# smoothie_ramps.net
KiCad netlist of a schematic drawn in EAGLE
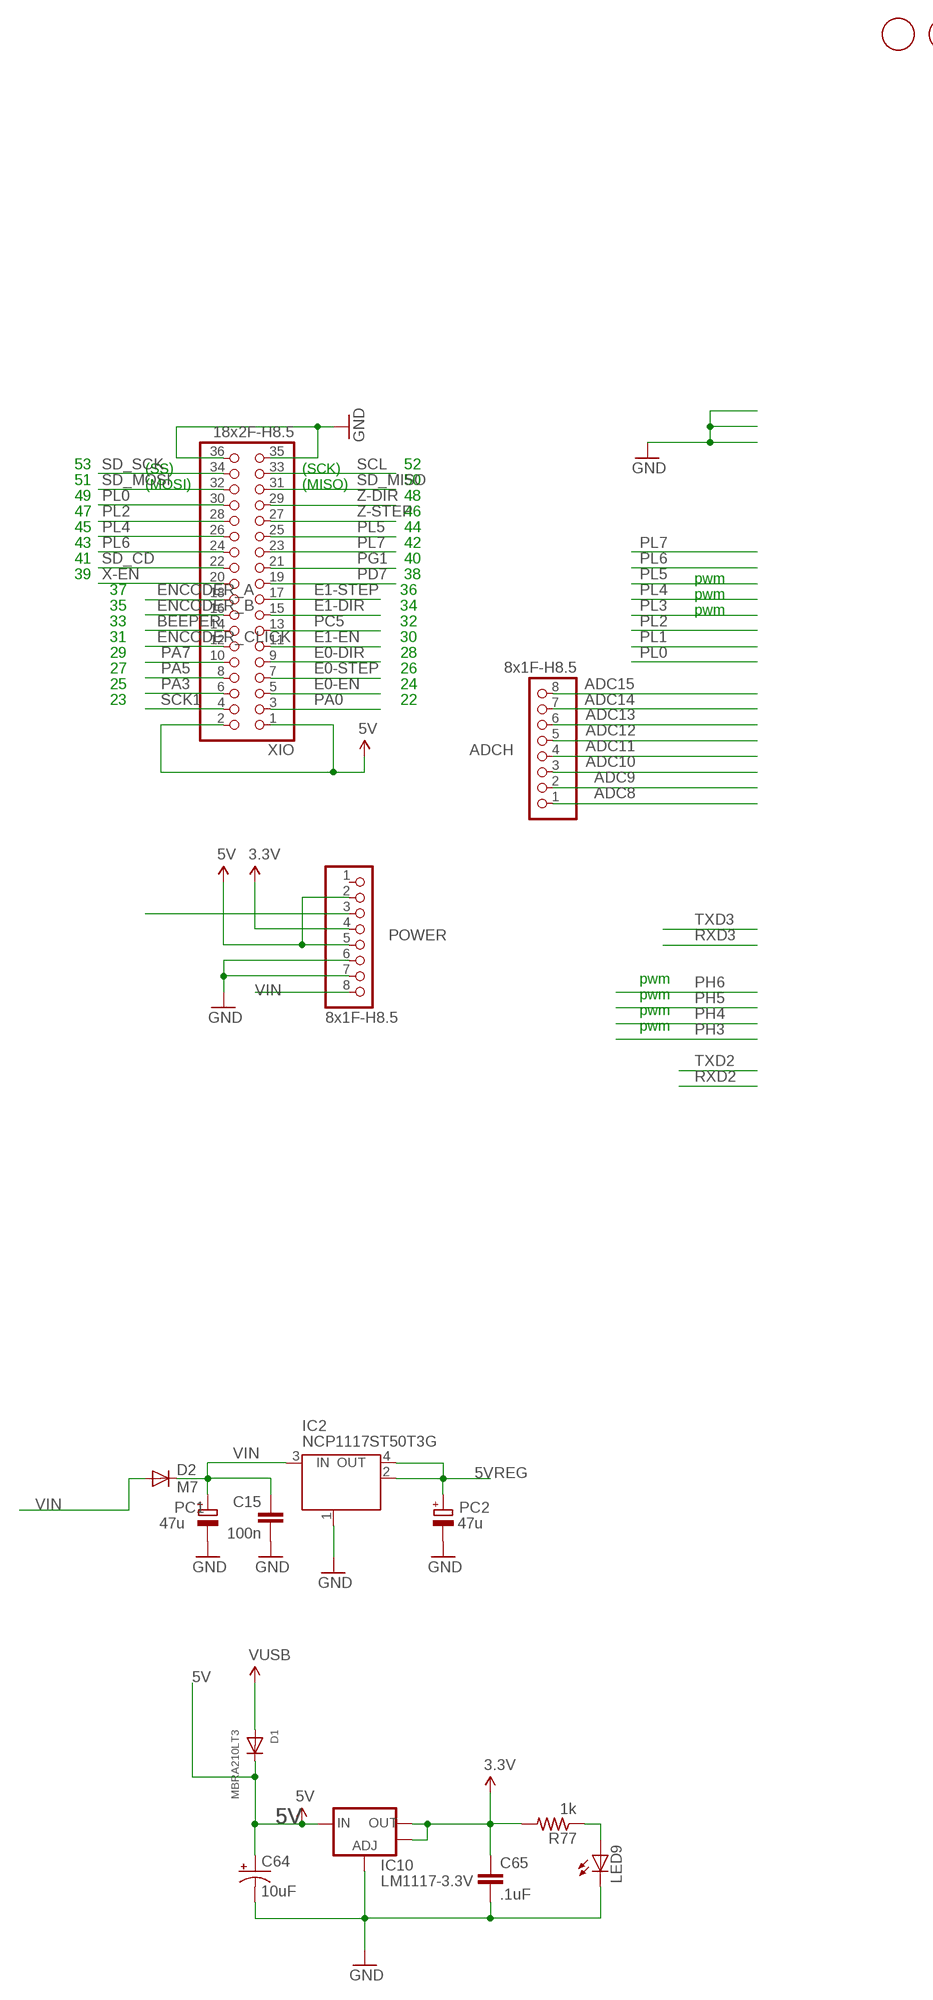
[diagram p0: schematic, sheet 1, part 1 of 2]
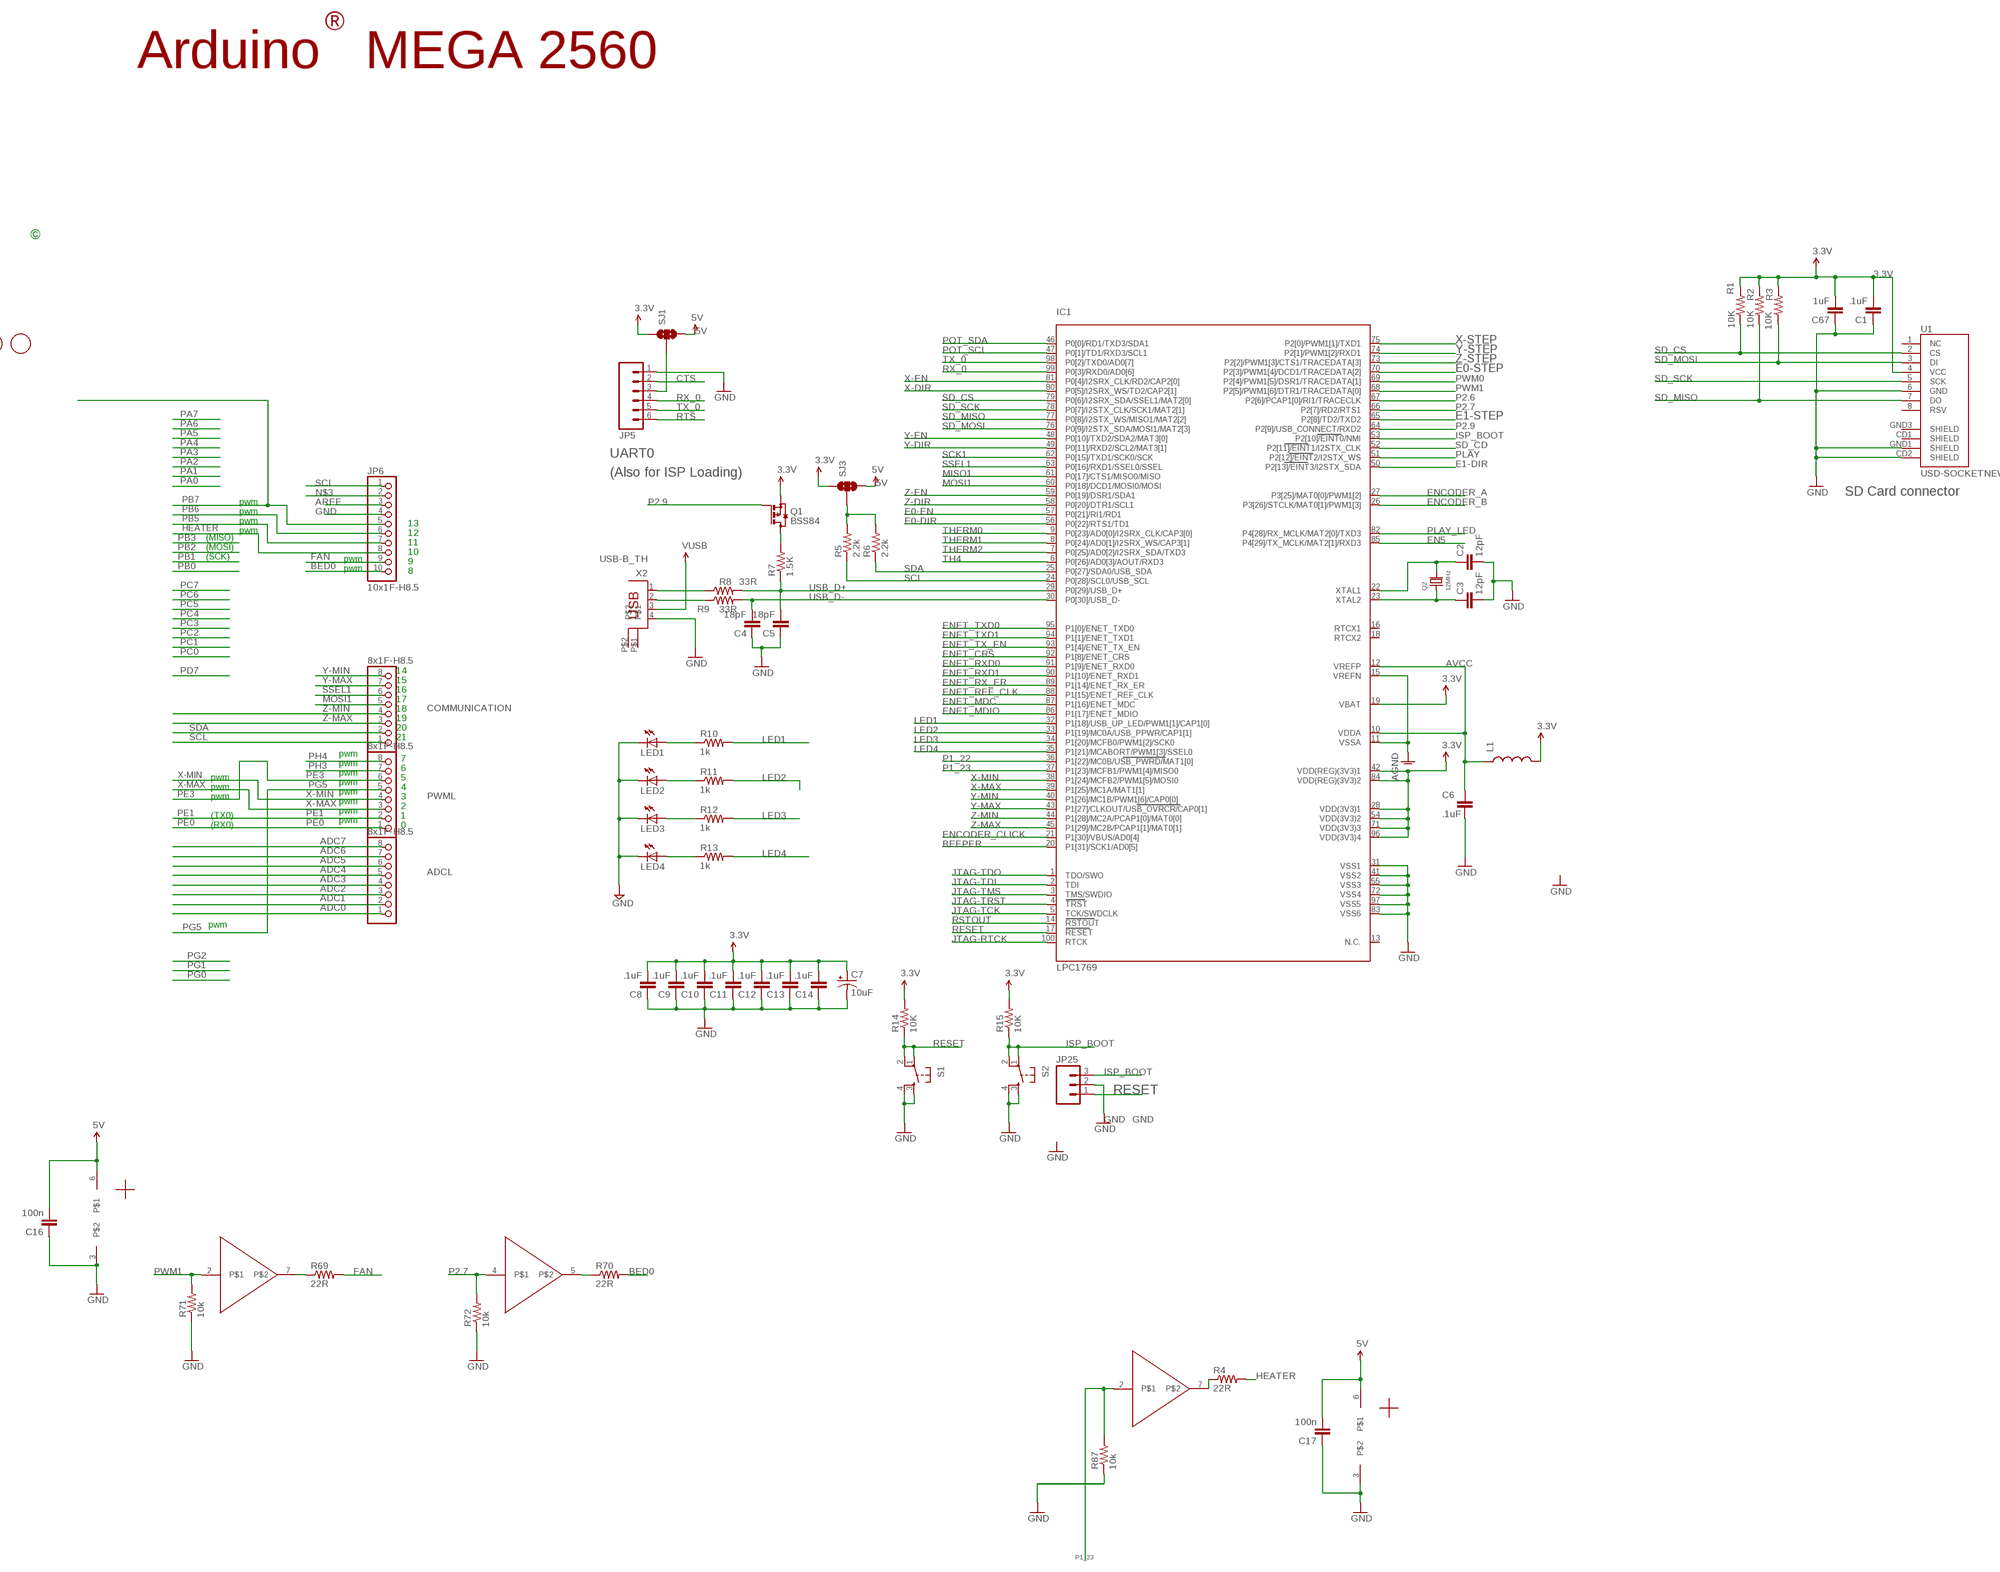
[diagram p1: schematic, sheet 1, part 2 of 2]

(export (version "E")
  (design (tool "Eeschema 10.0.6"))
  (components
    (comp (ref "ADCH")
      (value "8x1F-H8.5")
      (footprint "eagle-import:1X08")
      (libsource (lib "eagle-import") (part "PINHD-1X8"))
    )
    (comp (ref "ADCL")
      (value "8x1F-H8.5")
      (footprint "eagle-import:1X08")
      (libsource (lib "eagle-import") (part "PINHD-1X8"))
    )
    (comp (ref "C1")
      (value ".1uF")
      (footprint "eagle-import:C0603")
      (libsource (lib "eagle-import") (part "resistor_C-EUC0603"))
    )
    (comp (ref "C2")
      (value "12pF")
      (footprint "eagle-import:C0603")
      (libsource (lib "eagle-import") (part "rcl_C-EUC0603"))
    )
    (comp (ref "C3")
      (value "12pF")
      (footprint "eagle-import:C0603")
      (libsource (lib "eagle-import") (part "rcl_C-EUC0603"))
    )
    (comp (ref "C4")
      (value "18pF")
      (footprint "eagle-import:C0603")
      (libsource (lib "eagle-import") (part "rcl_C-EUC0603"))
    )
    (comp (ref "C5")
      (value "18pF")
      (footprint "eagle-import:C0603")
      (libsource (lib "eagle-import") (part "rcl_C-EUC0603"))
    )
    (comp (ref "C6")
      (value ".1uF")
      (footprint "eagle-import:C0603")
      (libsource (lib "eagle-import") (part "rcl_C-EUC0603"))
    )
    (comp (ref "C7")
      (value "10uF")
      (footprint "eagle-import:EIA3216")
      (libsource (lib "eagle-import") (part "CAP_POL1206"))
    )
    (comp (ref "C8")
      (value ".1uF")
      (footprint "eagle-import:C0603")
      (libsource (lib "eagle-import") (part "rcl_C-EUC0603"))
    )
    (comp (ref "C9")
      (value ".1uF")
      (footprint "eagle-import:C0603")
      (libsource (lib "eagle-import") (part "rcl_C-EUC0603"))
    )
    (comp (ref "C10")
      (value ".1uF")
      (footprint "eagle-import:C0603")
      (libsource (lib "eagle-import") (part "rcl_C-EUC0603"))
    )
    (comp (ref "C11")
      (value ".1uF")
      (footprint "eagle-import:C0603")
      (libsource (lib "eagle-import") (part "rcl_C-EUC0603"))
    )
    (comp (ref "C12")
      (value ".1uF")
      (footprint "eagle-import:C0603")
      (libsource (lib "eagle-import") (part "rcl_C-EUC0603"))
    )
    (comp (ref "C13")
      (value ".1uF")
      (footprint "eagle-import:C0603")
      (libsource (lib "eagle-import") (part "rcl_C-EUC0603"))
    )
    (comp (ref "C14")
      (value ".1uF")
      (footprint "eagle-import:C0603")
      (libsource (lib "eagle-import") (part "rcl_C-EUC0603"))
    )
    (comp (ref "C15")
      (value "100n")
      (footprint "eagle-import:C0603-ROUND")
      (libsource (lib "eagle-import") (part "C-EU0603-RND"))
    )
    (comp (ref "C16")
      (value "100n")
      (footprint "eagle-import:C0603")
      (libsource (lib "eagle-import") (part "rcl_C-EUC0603"))
    )
    (comp (ref "C17")
      (value "100n")
      (footprint "eagle-import:C0603")
      (libsource (lib "eagle-import") (part "rcl_C-EUC0603"))
    )
    (comp (ref "C64")
      (value "10uF")
      (footprint "eagle-import:EIA3216")
      (libsource (lib "eagle-import") (part "CAP_POL1206"))
    )
    (comp (ref "C65")
      (value ".1uF")
      (footprint "eagle-import:C0603")
      (libsource (lib "eagle-import") (part "resistor_C-EUC0603"))
    )
    (comp (ref "C67")
      (value "1uF")
      (footprint "eagle-import:C0805")
      (libsource (lib "eagle-import") (part "resistor_C-EUC0805"))
    )
    (comp (ref "COMMUNICATION")
      (value "8x1F-H8.5")
      (footprint "eagle-import:1X08")
      (libsource (lib "eagle-import") (part "PINHD-1X8"))
    )
    (comp (ref "D1")
      (value "MBRA210LT3")
      (footprint "eagle-import:SMADIODE")
      (libsource (lib "eagle-import") (part "DIODESMA"))
    )
    (comp (ref "D2")
      (value "M7")
      (footprint "eagle-import:SMB")
      (libsource (lib "eagle-import") (part "DIODE-SMB"))
    )
    (comp (ref "FD2")
      (value "FIDUCIALMOUNT")
      (footprint "eagle-import:FIDUCIA-MOUNT")
      (libsource (lib "eagle-import") (part "FIDUCIALMOUNT"))
    )
    (comp (ref "FD3")
      (value "FIDUCIALMOUNT")
      (footprint "eagle-import:FIDUCIA-MOUNT")
      (libsource (lib "eagle-import") (part "FIDUCIALMOUNT"))
    )
    (comp (ref "IC1")
      (value "LPC1769")
      (footprint "eagle-import:LQFP100")
      (libsource (lib "eagle-import") (part "LPC1768"))
    )
    (comp (ref "IC2")
      (value "NCP1117ST50T3G")
      (footprint "eagle-import:SOT223")
      (libsource (lib "eagle-import") (part "MC33269ST-3.3T3"))
    )
    (comp (ref "IC10")
      (value "LM1117-3.3V")
      (footprint "eagle-import:SOT223")
      (libsource (lib "eagle-import") (part "V_REG_LM1117SOT223"))
    )
    (comp (ref "IC14")
      (value "TC4427")
      (footprint "eagle-import:SOIC8")
      (libsource (lib "eagle-import") (part "TC4427"))
    )
    (comp (ref "IC15")
      (value "TC4427")
      (footprint "eagle-import:SOIC8")
      (libsource (lib "eagle-import") (part "TC4427"))
    )
    (comp (ref "JP5")
      (value "M06POLAR")
      (footprint "eagle-import:MOLEX-1X6")
      (libsource (lib "eagle-import") (part "M06POLAR"))
    )
    (comp (ref "JP6")
      (value "10x1F-H8.5")
      (footprint "eagle-import:1X10")
      (libsource (lib "eagle-import") (part "PINHD-1X10_ARD"))
    )
    (comp (ref "JP25")
      (value "M03PTH")
      (footprint "eagle-import:1X03")
      (libsource (lib "eagle-import") (part "M03PTH"))
    )
    (comp (ref "L1")
      (value "INDUCTOR0603")
      (footprint "eagle-import:0603")
      (libsource (lib "eagle-import") (part "INDUCTOR0603"))
    )
    (comp (ref "LED1")
      (value "LEDCHIP-LED0805")
      (footprint "eagle-import:CHIP-LED0805")
      (libsource (lib "eagle-import") (part "LEDCHIP-LED0805"))
    )
    (comp (ref "LED2")
      (value "LEDCHIP-LED0805")
      (footprint "eagle-import:CHIP-LED0805")
      (libsource (lib "eagle-import") (part "LEDCHIP-LED0805"))
    )
    (comp (ref "LED3")
      (value "LEDCHIP-LED0805")
      (footprint "eagle-import:CHIP-LED0805")
      (libsource (lib "eagle-import") (part "LEDCHIP-LED0805"))
    )
    (comp (ref "LED4")
      (value "LEDCHIP-LED0805")
      (footprint "eagle-import:CHIP-LED0805")
      (libsource (lib "eagle-import") (part "LEDCHIP-LED0805"))
    )
    (comp (ref "LED9")
      (value "LEDCHIP-LED0805")
      (footprint "eagle-import:CHIP-LED0805")
      (libsource (lib "eagle-import") (part "LEDCHIP-LED0805"))
    )
    (comp (ref "PC1")
      (value "47u")
      (footprint "eagle-import:PANASONIC_D")
      (libsource (lib "eagle-import") (part "CPOL-EUD"))
    )
    (comp (ref "PC2")
      (value "47u")
      (footprint "eagle-import:PANASONIC_D")
      (libsource (lib "eagle-import") (part "CPOL-EUD"))
    )
    (comp (ref "POWER")
      (value "8x1F-H8.5")
      (footprint "eagle-import:1X08")
      (libsource (lib "eagle-import") (part "PINHD-1X8"))
    )
    (comp (ref "PWML")
      (value "8x1F-H8.5")
      (footprint "eagle-import:1X08")
      (libsource (lib "eagle-import") (part "PINHD-1X8"))
    )
    (comp (ref "Q1")
      (value "BSS84")
      (footprint "eagle-import:SOT23")
      (libsource (lib "eagle-import") (part "BSS84"))
    )
    (comp (ref "Q2")
      (value "12MHz")
      (footprint "eagle-import:CRYSTAL_3.2X2.5")
      (libsource (lib "eagle-import") (part "CRYSTALTHIN"))
    )
    (comp (ref "R1")
      (value "10K")
      (footprint "eagle-import:R0603")
      (libsource (lib "eagle-import") (part "R-US_R0603"))
    )
    (comp (ref "R2")
      (value "10K")
      (footprint "eagle-import:R0603")
      (libsource (lib "eagle-import") (part "R-US_R0603"))
    )
    (comp (ref "R3")
      (value "10K")
      (footprint "eagle-import:R0603")
      (libsource (lib "eagle-import") (part "R-US_R0603"))
    )
    (comp (ref "R4")
      (value "22R")
      (footprint "eagle-import:R0603")
      (libsource (lib "eagle-import") (part "R-US_R0603"))
    )
    (comp (ref "R5")
      (value "2.2k")
      (footprint "eagle-import:R0603")
      (libsource (lib "eagle-import") (part "R-US_R0603"))
    )
    (comp (ref "R6")
      (value "2.2k")
      (footprint "eagle-import:R0603")
      (libsource (lib "eagle-import") (part "R-US_R0603"))
    )
    (comp (ref "R7")
      (value "1.5K")
      (footprint "eagle-import:R0603")
      (libsource (lib "eagle-import") (part "R-US_R0603"))
    )
    (comp (ref "R8")
      (value "33R")
      (footprint "eagle-import:R0603")
      (libsource (lib "eagle-import") (part "R-US_R0603"))
    )
    (comp (ref "R9")
      (value "33R")
      (footprint "eagle-import:R0603")
      (libsource (lib "eagle-import") (part "R-US_R0603"))
    )
    (comp (ref "R10")
      (value "1k")
      (footprint "eagle-import:R0603")
      (libsource (lib "eagle-import") (part "R-US_R0603"))
    )
    (comp (ref "R11")
      (value "1k")
      (footprint "eagle-import:R0603")
      (libsource (lib "eagle-import") (part "R-US_R0603"))
    )
    (comp (ref "R12")
      (value "1k")
      (footprint "eagle-import:R0603")
      (libsource (lib "eagle-import") (part "R-US_R0603"))
    )
    (comp (ref "R13")
      (value "1k")
      (footprint "eagle-import:R0603")
      (libsource (lib "eagle-import") (part "R-US_R0603"))
    )
    (comp (ref "R14")
      (value "10K")
      (footprint "eagle-import:R0603")
      (libsource (lib "eagle-import") (part "R-US_R0603"))
    )
    (comp (ref "R15")
      (value "10K")
      (footprint "eagle-import:R0603")
      (libsource (lib "eagle-import") (part "R-US_R0603"))
    )
    (comp (ref "R69")
      (value "22R")
      (footprint "eagle-import:R0603")
      (libsource (lib "eagle-import") (part "R-US_R0603"))
    )
    (comp (ref "R70")
      (value "22R")
      (footprint "eagle-import:R0603")
      (libsource (lib "eagle-import") (part "R-US_R0603"))
    )
    (comp (ref "R71")
      (value "10k")
      (footprint "eagle-import:R0603")
      (libsource (lib "eagle-import") (part "R-US_R0603"))
    )
    (comp (ref "R72")
      (value "10k")
      (footprint "eagle-import:R0603")
      (libsource (lib "eagle-import") (part "R-US_R0603"))
    )
    (comp (ref "R77")
      (value "1k")
      (footprint "eagle-import:R0603")
      (libsource (lib "eagle-import") (part "R-US_R0603"))
    )
    (comp (ref "R87")
      (value "10k")
      (footprint "eagle-import:R0603")
      (libsource (lib "eagle-import") (part "R-US_R0603"))
    )
    (comp (ref "S1")
      (value "TAC_SWITCHSMD")
      (footprint "eagle-import:TACTILE_SWITCH_SMD")
      (libsource (lib "eagle-import") (part "TAC_SWITCHSMD"))
    )
    (comp (ref "S2")
      (value "TAC_SWITCHSMD")
      (footprint "eagle-import:TACTILE_SWITCH_SMD")
      (libsource (lib "eagle-import") (part "TAC_SWITCHSMD"))
    )
    (comp (ref "SJ1")
      (value "SOLDERJUMPER_2WAYS")
      (footprint "eagle-import:SJ_3")
      (libsource (lib "eagle-import") (part "SOLDERJUMPER_2WAYS"))
    )
    (comp (ref "SJ3")
      (value "SOLDERJUMPER_2WAYS")
      (footprint "eagle-import:SJ_3")
      (libsource (lib "eagle-import") (part "SOLDERJUMPER_2WAYS"))
    )
    (comp (ref "U1")
      (value "USD-SOCKETNEW")
      (footprint "eagle-import:MICRO-SD-SOCKET-PP")
      (libsource (lib "eagle-import") (part "USD-SOCKETNEW"))
    )
    (comp (ref "X2")
      (value "USB-B_TH")
      (footprint "eagle-import:PN61729")
      (libsource (lib "eagle-import") (part "PN61729"))
    )
    (comp (ref "XIO")
      (value "18x2F-H8.5")
      (footprint "eagle-import:2X18")
      (libsource (lib "eagle-import") (part "PINHD-2X18"))
    )
  )
  (nets
    (net (code "1") (name "/5VREG") (class "Default")
      (node (ref "IC2") (pin "2") (pinfunction "OUT_2") (pintype "passive"))
      (node (ref "IC2") (pin "4") (pinfunction "OUT_4") (pintype "passive"))
      (node (ref "PC2") (pin "+") (pinfunction "+_+") (pintype "passive"))
    )
    (net (code "2") (name "/ADC0") (class "Default")
      (node (ref "ADCL") (pin "1") (pinfunction "1_1") (pintype "passive"))
    )
    (net (code "3") (name "/ADC1") (class "Default")
      (node (ref "ADCL") (pin "2") (pinfunction "2_2") (pintype "passive"))
    )
    (net (code "4") (name "/ADC2") (class "Default")
      (node (ref "ADCL") (pin "3") (pinfunction "3_3") (pintype "passive"))
    )
    (net (code "5") (name "/ADC3") (class "Default")
      (node (ref "ADCL") (pin "4") (pinfunction "4_4") (pintype "passive"))
    )
    (net (code "6") (name "/ADC4") (class "Default")
      (node (ref "ADCL") (pin "5") (pinfunction "5_5") (pintype "passive"))
    )
    (net (code "7") (name "/ADC5") (class "Default")
      (node (ref "ADCL") (pin "6") (pinfunction "6_6") (pintype "passive"))
    )
    (net (code "8") (name "/ADC6") (class "Default")
      (node (ref "ADCL") (pin "7") (pinfunction "7_7") (pintype "passive"))
    )
    (net (code "9") (name "/ADC7") (class "Default")
      (node (ref "ADCL") (pin "8") (pinfunction "8_8") (pintype "passive"))
    )
    (net (code "10") (name "/ADC8") (class "Default")
      (node (ref "ADCH") (pin "1") (pinfunction "1_1") (pintype "passive"))
    )
    (net (code "11") (name "/ADC9") (class "Default")
      (node (ref "ADCH") (pin "2") (pinfunction "2_2") (pintype "passive"))
    )
    (net (code "12") (name "/ADC10") (class "Default")
      (node (ref "ADCH") (pin "3") (pinfunction "3_3") (pintype "passive"))
    )
    (net (code "13") (name "/ADC11") (class "Default")
      (node (ref "ADCH") (pin "4") (pinfunction "4_4") (pintype "passive"))
    )
    (net (code "14") (name "/ADC12") (class "Default")
      (node (ref "ADCH") (pin "5") (pinfunction "5_5") (pintype "passive"))
    )
    (net (code "15") (name "/ADC13") (class "Default")
      (node (ref "ADCH") (pin "6") (pinfunction "6_6") (pintype "passive"))
    )
    (net (code "16") (name "/ADC14") (class "Default")
      (node (ref "ADCH") (pin "7") (pinfunction "7_7") (pintype "passive"))
    )
    (net (code "17") (name "/ADC15") (class "Default")
      (node (ref "ADCH") (pin "8") (pinfunction "8_8") (pintype "passive"))
    )
    (net (code "18") (name "/AREF") (class "Default")
      (node (ref "JP6") (pin "3") (pinfunction "3_3") (pintype "passive"))
    )
    (net (code "19") (name "/AVCC") (class "Default")
      (node (ref "C6") (pin "1") (pinfunction "1_1") (pintype "passive"))
      (node (ref "IC1") (pin "10") (pinfunction "VDDA_10") (pintype "bidirectional"))
      (node (ref "IC1") (pin "12") (pinfunction "VREFP_12") (pintype "bidirectional"))
      (node (ref "L1") (pin "1") (pinfunction "1_1") (pintype "passive"))
    )
    (net (code "20") (name "/BED0") (class "Default")
      (node (ref "JP6") (pin "10") (pinfunction "10_10") (pintype "passive"))
      (node (ref "R70") (pin "2") (pinfunction "2_2") (pintype "passive"))
    )
    (net (code "21") (name "/BEEPER") (class "Default")
      (node (ref "IC1") (pin "20") (pinfunction "P1[31]/SCK1/AD0[5]_20") (pintype "bidirectional"))
      (node (ref "XIO") (pin "14") (pinfunction "14_14") (pintype "passive"))
    )
    (net (code "22") (name "/CTS") (class "Default")
      (node (ref "JP5") (pin "2") (pinfunction "2_2") (pintype "passive"))
    )
    (net (code "23") (name "/E0-DIR") (class "Default")
      (node (ref "IC1") (pin "56") (pinfunction "P0[22]/RTS1/TD1_56") (pintype "bidirectional"))
      (node (ref "XIO") (pin "9") (pinfunction "9_9") (pintype "passive"))
    )
    (net (code "24") (name "/E0-EN") (class "Default")
      (node (ref "IC1") (pin "57") (pinfunction "P0[21]/RI1/RD1_57") (pintype "bidirectional"))
      (node (ref "XIO") (pin "5") (pinfunction "5_5") (pintype "passive"))
    )
    (net (code "25") (name "/E0-STEP") (class "Default")
      (node (ref "IC1") (pin "70") (pinfunction "P2[3]/PWM1[4]/DCD1/TRACEDATA[2]_70") (pintype "bidirectional"))
      (node (ref "XIO") (pin "7") (pinfunction "7_7") (pintype "passive"))
    )
    (net (code "26") (name "/E1-DIR") (class "Default")
      (node (ref "IC1") (pin "50") (pinfunction "P2[13]/EINT3/I2STX_SDA_50") (pintype "bidirectional"))
      (node (ref "XIO") (pin "15") (pinfunction "15_15") (pintype "passive"))
    )
    (net (code "27") (name "/E1-EN") (class "Default")
      (node (ref "XIO") (pin "11") (pinfunction "11_11") (pintype "passive"))
    )
    (net (code "28") (name "/E1-STEP") (class "Default")
      (node (ref "IC1") (pin "65") (pinfunction "P2[8]/TD2/TXD2_65") (pintype "bidirectional"))
      (node (ref "XIO") (pin "17") (pinfunction "17_17") (pintype "passive"))
    )
    (net (code "29") (name "/EN5") (class "Default")
      (node (ref "IC1") (pin "85") (pinfunction "P4[29]/TX_MCLK/MAT2[1]/RXD3_85") (pintype "bidirectional"))
    )
    (net (code "30") (name "/ENCODER_A") (class "Default")
      (node (ref "IC1") (pin "27") (pinfunction "P3[25]/MAT0[0]/PWM1[2]_27") (pintype "bidirectional"))
      (node (ref "XIO") (pin "18") (pinfunction "18_18") (pintype "passive"))
    )
    (net (code "31") (name "/ENCODER_B") (class "Default")
      (node (ref "IC1") (pin "26") (pinfunction "P3[26]/STCLK/MAT0[1]/PWM1[3]_26") (pintype "bidirectional"))
      (node (ref "XIO") (pin "16") (pinfunction "16_16") (pintype "passive"))
    )
    (net (code "32") (name "/ENCODER_CLICK") (class "Default")
      (node (ref "IC1") (pin "21") (pinfunction "P1[30]/VBUS/AD0[4]_21") (pintype "bidirectional"))
      (node (ref "XIO") (pin "12") (pinfunction "12_12") (pintype "passive"))
    )
    (net (code "33") (name "/ENET_CRS") (class "Default")
      (node (ref "IC1") (pin "92") (pinfunction "P1[8]/ENET_CRS_92") (pintype "bidirectional"))
    )
    (net (code "34") (name "/ENET_MDC") (class "Default")
      (node (ref "IC1") (pin "87") (pinfunction "P1[16]/ENET_MDC_87") (pintype "bidirectional"))
    )
    (net (code "35") (name "/ENET_MDIO") (class "Default")
      (node (ref "IC1") (pin "86") (pinfunction "P1[17]/ENET_MDIO_86") (pintype "bidirectional"))
    )
    (net (code "36") (name "/ENET_REF_CLK") (class "Default")
      (node (ref "IC1") (pin "88") (pinfunction "P1[15]/ENET_REF_CLK_88") (pintype "bidirectional"))
    )
    (net (code "37") (name "/ENET_RXD0") (class "Default")
      (node (ref "IC1") (pin "91") (pinfunction "P1[9]/ENET_RXD0_91") (pintype "bidirectional"))
    )
    (net (code "38") (name "/ENET_RXD1") (class "Default")
      (node (ref "IC1") (pin "90") (pinfunction "P1[10]/ENET_RXD1_90") (pintype "bidirectional"))
    )
    (net (code "39") (name "/ENET_RX_ER") (class "Default")
      (node (ref "IC1") (pin "89") (pinfunction "P1[14]/ENET_RX_ER_89") (pintype "bidirectional"))
    )
    (net (code "40") (name "/ENET_TXD0") (class "Default")
      (node (ref "IC1") (pin "95") (pinfunction "P1[0]/ENET_TXD0_95") (pintype "bidirectional"))
    )
    (net (code "41") (name "/ENET_TXD1") (class "Default")
      (node (ref "IC1") (pin "94") (pinfunction "P1[1]/ENET_TXD1_94") (pintype "bidirectional"))
    )
    (net (code "42") (name "/ENET_TX_EN") (class "Default")
      (node (ref "IC1") (pin "93") (pinfunction "P1[4]/ENET_TX_EN_93") (pintype "bidirectional"))
    )
    (net (code "43") (name "/FAN") (class "Default")
      (node (ref "JP6") (pin "9") (pinfunction "9_9") (pintype "passive"))
      (node (ref "R69") (pin "2") (pinfunction "2_2") (pintype "passive"))
    )
    (net (code "44") (name "/HEATER") (class "Default")
      (node (ref "JP6") (pin "8") (pinfunction "8_8") (pintype "passive"))
      (node (ref "R4") (pin "2") (pinfunction "2_2") (pintype "passive"))
    )
    (net (code "45") (name "/ISP_BOOT") (class "Default")
      (node (ref "IC1") (pin "53") (pinfunction "P2[10]/EINT0/NMI_53") (pintype "bidirectional"))
      (node (ref "JP25") (pin "3") (pinfunction "3_3") (pintype "passive"))
      (node (ref "R15") (pin "1") (pinfunction "1_1") (pintype "passive"))
      (node (ref "S2") (pin "1") (pinfunction "1_1") (pintype "passive"))
      (node (ref "S2") (pin "2") (pinfunction "2_2") (pintype "passive"))
    )
    (net (code "46") (name "/JTAG-RTCK") (class "Default")
      (node (ref "IC1") (pin "100") (pinfunction "RTCK_100") (pintype "bidirectional"))
    )
    (net (code "47") (name "/JTAG-TCK") (class "Default")
      (node (ref "IC1") (pin "5") (pinfunction "TCK/SWDCLK_5") (pintype "bidirectional"))
    )
    (net (code "48") (name "/JTAG-TDI") (class "Default")
      (node (ref "IC1") (pin "2") (pinfunction "TDI_2") (pintype "bidirectional"))
    )
    (net (code "49") (name "/JTAG-TDO") (class "Default")
      (node (ref "IC1") (pin "1") (pinfunction "TDO/SWO_1") (pintype "bidirectional"))
    )
    (net (code "50") (name "/JTAG-TMS") (class "Default")
      (node (ref "IC1") (pin "3") (pinfunction "TMS/SWDIO_3") (pintype "bidirectional"))
    )
    (net (code "51") (name "/JTAG-TRST") (class "Default")
      (node (ref "IC1") (pin "4") (pinfunction "TRST_4") (pintype "bidirectional"))
    )
    (net (code "52") (name "/LED1") (class "Default")
      (node (ref "IC1") (pin "32") (pinfunction "P1[18]/USB_UP_LED/PWM1[1]/CAP1[0]_32") (pintype "bidirectional"))
      (node (ref "R10") (pin "2") (pinfunction "2_2") (pintype "passive"))
    )
    (net (code "53") (name "/LED2") (class "Default")
      (node (ref "IC1") (pin "33") (pinfunction "P1[19]/MC0A/USB_PPWR/CAP1[1]_33") (pintype "bidirectional"))
      (node (ref "R11") (pin "2") (pinfunction "2_2") (pintype "passive"))
    )
    (net (code "54") (name "/LED3") (class "Default")
      (node (ref "IC1") (pin "34") (pinfunction "P1[20]/MCFB0/PWM1[2]/SCK0_34") (pintype "bidirectional"))
      (node (ref "R12") (pin "2") (pinfunction "2_2") (pintype "passive"))
    )
    (net (code "55") (name "/LED4") (class "Default")
      (node (ref "IC1") (pin "35") (pinfunction "P1[21]/MCABORT/PWM1[3]/SSEL0_35") (pintype "bidirectional"))
      (node (ref "R13") (pin "2") (pinfunction "2_2") (pintype "passive"))
    )
    (net (code "56") (name "/MISO1") (class "Default")
      (node (ref "IC1") (pin "61") (pinfunction "P0[17]/CTS1/MISO0/MISO_61") (pintype "bidirectional"))
    )
    (net (code "57") (name "/MOSI1") (class "Default")
      (node (ref "COMMUNICATION") (pin "5") (pinfunction "5_5") (pintype "passive"))
      (node (ref "IC1") (pin "60") (pinfunction "P0[18]/DCD1/MOSI0/MOSI_60") (pintype "bidirectional"))
    )
    (net (code "58") (name "/N$3") (class "Default")
      (node (ref "JP6") (pin "2") (pinfunction "2_2") (pintype "passive"))
    )
    (net (code "59") (name "/P1_22") (class "Default")
      (node (ref "IC1") (pin "36") (pinfunction "P1[22]/MC0B/USB_PWRD/MAT1[0]_36") (pintype "bidirectional"))
    )
    (net (code "60") (name "/P1_23") (class "Default")
      (node (ref "IC1") (pin "37") (pinfunction "P1[23]/MCFB1/PWM1[4]/MISO0_37") (pintype "bidirectional"))
      (node (ref "IC15") (pin "2") (pinfunction "P$1_2") (pintype "bidirectional"))
      (node (ref "R87") (pin "2") (pinfunction "2_2") (pintype "passive"))
    )
    (net (code "61") (name "/P2.6") (class "Default")
      (node (ref "IC1") (pin "67") (pinfunction "P2[6]/PCAP1[0]/RI1/TRACECLK_67") (pintype "bidirectional"))
    )
    (net (code "62") (name "/P2.7") (class "Default")
      (node (ref "IC1") (pin "66") (pinfunction "P2[7]/RD2/RTS1_66") (pintype "bidirectional"))
      (node (ref "IC14") (pin "4") (pinfunction "P$1_4") (pintype "bidirectional"))
      (node (ref "R72") (pin "2") (pinfunction "2_2") (pintype "passive"))
    )
    (net (code "63") (name "/P2.9") (class "Default")
      (node (ref "IC1") (pin "64") (pinfunction "P2[9]/USB_CONNECT/RXD2_64") (pintype "bidirectional"))
      (node (ref "Q1") (pin "1") (pinfunction "G_1") (pintype "passive"))
    )
    (net (code "64") (name "/PA0") (class "Default")
      (node (ref "XIO") (pin "3") (pinfunction "3_3") (pintype "passive"))
    )
    (net (code "67") (name "/PA3") (class "Default")
      (node (ref "XIO") (pin "6") (pinfunction "6_6") (pintype "passive"))
    )
    (net (code "69") (name "/PA5") (class "Default")
      (node (ref "XIO") (pin "8") (pinfunction "8_8") (pintype "passive"))
    )
    (net (code "71") (name "/PA7") (class "Default")
      (node (ref "XIO") (pin "10") (pinfunction "10_10") (pintype "passive"))
    )
    (net (code "76") (name "/PB5") (class "Default")
      (node (ref "JP6") (pin "7") (pinfunction "7_7") (pintype "passive"))
    )
    (net (code "77") (name "/PB6") (class "Default")
      (node (ref "JP6") (pin "6") (pinfunction "6_6") (pintype "passive"))
    )
    (net (code "78") (name "/PB7") (class "Default")
      (node (ref "JP6") (pin "5") (pinfunction "5_5") (pintype "passive"))
    )
    (net (code "84") (name "/PC5") (class "Default")
      (node (ref "XIO") (pin "13") (pinfunction "13_13") (pintype "passive"))
    )
    (net (code "87") (name "/PD7") (class "Default")
      (node (ref "XIO") (pin "19") (pinfunction "19_19") (pintype "passive"))
    )
    (net (code "88") (name "/PE0") (class "Default")
      (node (ref "PWML") (pin "1") (pinfunction "1_1") (pintype "passive"))
    )
    (net (code "89") (name "/PE1") (class "Default")
      (node (ref "PWML") (pin "2") (pinfunction "2_2") (pintype "passive"))
    )
    (net (code "90") (name "/PE3") (class "Default")
      (node (ref "PWML") (pin "6") (pinfunction "6_6") (pintype "passive"))
    )
    (net (code "92") (name "/PG1") (class "Default")
      (node (ref "XIO") (pin "21") (pinfunction "21_21") (pintype "passive"))
    )
    (net (code "94") (name "/PG5") (class "Default")
      (node (ref "PWML") (pin "5") (pinfunction "5_5") (pintype "passive"))
    )
    (net (code "95") (name "/PH3") (class "Default")
      (node (ref "PWML") (pin "7") (pinfunction "7_7") (pintype "passive"))
    )
    (net (code "96") (name "/PH4") (class "Default")
      (node (ref "PWML") (pin "8") (pinfunction "8_8") (pintype "passive"))
    )
    (net (code "99") (name "/PL0") (class "Default")
      (node (ref "XIO") (pin "30") (pinfunction "30_30") (pintype "passive"))
    )
    (net (code "101") (name "/PL2") (class "Default")
      (node (ref "XIO") (pin "28") (pinfunction "28_28") (pintype "passive"))
    )
    (net (code "103") (name "/PL4") (class "Default")
      (node (ref "XIO") (pin "26") (pinfunction "26_26") (pintype "passive"))
    )
    (net (code "104") (name "/PL5") (class "Default")
      (node (ref "XIO") (pin "25") (pinfunction "25_25") (pintype "passive"))
    )
    (net (code "105") (name "/PL6") (class "Default")
      (node (ref "XIO") (pin "24") (pinfunction "24_24") (pintype "passive"))
    )
    (net (code "106") (name "/PL7") (class "Default")
      (node (ref "XIO") (pin "23") (pinfunction "23_23") (pintype "passive"))
    )
    (net (code "107") (name "/PLAY") (class "Default")
      (node (ref "IC1") (pin "51") (pinfunction "P2[12]/EINT2/I2STX_WS_51") (pintype "bidirectional"))
    )
    (net (code "108") (name "/PLAY_LED") (class "Default")
      (node (ref "IC1") (pin "82") (pinfunction "P4[28]/RX_MCLK/MAT2[0]/TXD3_82") (pintype "bidirectional"))
    )
    (net (code "109") (name "/POT_SCL") (class "Default")
      (node (ref "IC1") (pin "47") (pinfunction "P0[1]/TD1/RXD3/SCL1_47") (pintype "bidirectional"))
    )
    (net (code "110") (name "/POT_SDA") (class "Default")
      (node (ref "IC1") (pin "46") (pinfunction "P0[0]/RD1/TXD3/SDA1_46") (pintype "bidirectional"))
    )
    (net (code "111") (name "/PWM0") (class "Default")
      (node (ref "IC1") (pin "69") (pinfunction "P2[4]/PWM1[5]/DSR1/TRACEDATA[1]_69") (pintype "bidirectional"))
    )
    (net (code "112") (name "/PWM1") (class "Default")
      (node (ref "IC1") (pin "68") (pinfunction "P2[5]/PWM1[6]/DTR1/TRACEDATA[0]_68") (pintype "bidirectional"))
      (node (ref "IC14") (pin "2") (pinfunction "P$1_2") (pintype "bidirectional"))
      (node (ref "R71") (pin "2") (pinfunction "2_2") (pintype "passive"))
    )
    (net (code "113") (name "/RESET") (class "Default")
      (node (ref "IC1") (pin "17") (pinfunction "RESET_17") (pintype "bidirectional"))
      (node (ref "JP25") (pin "1") (pinfunction "1_1") (pintype "passive"))
      (node (ref "POWER") (pin "3") (pinfunction "3_3") (pintype "passive"))
      (node (ref "R14") (pin "1") (pinfunction "1_1") (pintype "passive"))
      (node (ref "S1") (pin "1") (pinfunction "1_1") (pintype "passive"))
      (node (ref "S1") (pin "2") (pinfunction "2_2") (pintype "passive"))
    )
    (net (code "114") (name "/RSTOUT") (class "Default")
      (node (ref "IC1") (pin "14") (pinfunction "RSTOUT_14") (pintype "bidirectional"))
    )
    (net (code "115") (name "/RTS") (class "Default")
      (node (ref "JP5") (pin "6") (pinfunction "6_6") (pintype "passive"))
    )
    (net (code "118") (name "/RX_0") (class "Default")
      (node (ref "IC1") (pin "99") (pinfunction "P0[3]/RXD0/AD0[6]_99") (pintype "bidirectional"))
      (node (ref "JP5") (pin "4") (pinfunction "4_4") (pintype "passive"))
    )
    (net (code "119") (name "/SCK1") (class "Default")
      (node (ref "IC1") (pin "62") (pinfunction "P0[15]/TXD1/SCK0/SCK_62") (pintype "bidirectional"))
      (node (ref "XIO") (pin "4") (pinfunction "4_4") (pintype "passive"))
    )
    (net (code "120") (name "/SCL") (class "Default")
      (node (ref "COMMUNICATION") (pin "1") (pinfunction "1_1") (pintype "passive"))
      (node (ref "IC1") (pin "24") (pinfunction "P0[28]/SCL0/USB_SCL_24") (pintype "bidirectional"))
      (node (ref "JP6") (pin "1") (pinfunction "1_1") (pintype "passive"))
      (node (ref "R5") (pin "1") (pinfunction "1_1") (pintype "passive"))
      (node (ref "XIO") (pin "33") (pinfunction "33_33") (pintype "passive"))
    )
    (net (code "121") (name "/SDA") (class "Default")
      (node (ref "COMMUNICATION") (pin "2") (pinfunction "2_2") (pintype "passive"))
      (node (ref "IC1") (pin "25") (pinfunction "P0[27]/SDA0/USB_SDA_25") (pintype "bidirectional"))
      (node (ref "R6") (pin "1") (pinfunction "1_1") (pintype "passive"))
    )
    (net (code "122") (name "/SD_CD") (class "Default")
      (node (ref "IC1") (pin "52") (pinfunction "P2[11]/EINT1/I2STX_CLK_52") (pintype "bidirectional"))
      (node (ref "XIO") (pin "22") (pinfunction "22_22") (pintype "passive"))
    )
    (net (code "123") (name "/SD_CS") (class "Default")
      (node (ref "IC1") (pin "79") (pinfunction "P0[6]/I2SRX_SDA/SSEL1/MAT2[0]_79") (pintype "bidirectional"))
      (node (ref "R1") (pin "1") (pinfunction "1_1") (pintype "passive"))
      (node (ref "U1") (pin "2") (pinfunction "CS_2") (pintype "bidirectional"))
    )
    (net (code "124") (name "/SD_MISO") (class "Default")
      (node (ref "IC1") (pin "77") (pinfunction "P0[8]/I2STX_WS/MISO1/MAT2[2]_77") (pintype "bidirectional"))
      (node (ref "R2") (pin "1") (pinfunction "1_1") (pintype "passive"))
      (node (ref "U1") (pin "7") (pinfunction "DO_7") (pintype "bidirectional"))
      (node (ref "XIO") (pin "31") (pinfunction "31_31") (pintype "passive"))
    )
    (net (code "125") (name "/SD_MOSI") (class "Default")
      (node (ref "IC1") (pin "76") (pinfunction "P0[9]/I2STX_SDA/MOSI1/MAT2[3]_76") (pintype "bidirectional"))
      (node (ref "R3") (pin "1") (pinfunction "1_1") (pintype "passive"))
      (node (ref "U1") (pin "3") (pinfunction "DI_3") (pintype "bidirectional"))
      (node (ref "XIO") (pin "32") (pinfunction "32_32") (pintype "passive"))
    )
    (net (code "126") (name "/SD_SCK") (class "Default")
      (node (ref "IC1") (pin "78") (pinfunction "P0[7]/I2STX_CLK/SCK1/MAT2[1]_78") (pintype "bidirectional"))
      (node (ref "U1") (pin "5") (pinfunction "SCK_5") (pintype "bidirectional"))
      (node (ref "XIO") (pin "34") (pinfunction "34_34") (pintype "passive"))
    )
    (net (code "127") (name "/SSEL1") (class "Default")
      (node (ref "COMMUNICATION") (pin "6") (pinfunction "6_6") (pintype "passive"))
      (node (ref "IC1") (pin "63") (pinfunction "P0[16]/RXD1/SSEL0/SSEL_63") (pintype "bidirectional"))
    )
    (net (code "128") (name "/TH4") (class "Default")
      (node (ref "IC1") (pin "6") (pinfunction "P0[26]/AD0[3]/AOUT/RXD3_6") (pintype "bidirectional"))
    )
    (net (code "129") (name "/THERM0") (class "Default")
      (node (ref "IC1") (pin "9") (pinfunction "P0[23]/AD0[0]/I2SRX_CLK/CAP3[0]_9") (pintype "bidirectional"))
    )
    (net (code "130") (name "/THERM1") (class "Default")
      (node (ref "IC1") (pin "8") (pinfunction "P0[24]/AD0[1]/I2SRX_WS/CAP3[1]_8") (pintype "bidirectional"))
    )
    (net (code "131") (name "/THERM2") (class "Default")
      (node (ref "IC1") (pin "7") (pinfunction "P0[25]/AD0[2]/I2SRX_SDA/TXD3_7") (pintype "bidirectional"))
    )
    (net (code "134") (name "/TX_0") (class "Default")
      (node (ref "IC1") (pin "98") (pinfunction "P0[2]/TXD0/AD0[7]_98") (pintype "bidirectional"))
      (node (ref "JP5") (pin "5") (pinfunction "5_5") (pintype "passive"))
    )
    (net (code "135") (name "/USB_D+") (class "Default")
      (node (ref "C5") (pin "2") (pinfunction "2_2") (pintype "passive"))
      (node (ref "IC1") (pin "29") (pinfunction "P0[29]/USB_D+_29") (pintype "bidirectional"))
      (node (ref "R7") (pin "1") (pinfunction "1_1") (pintype "passive"))
      (node (ref "R8") (pin "2") (pinfunction "2_2") (pintype "passive"))
    )
    (net (code "136") (name "/USB_D-") (class "Default")
      (node (ref "C4") (pin "2") (pinfunction "2_2") (pintype "passive"))
      (node (ref "IC1") (pin "30") (pinfunction "P0[30]/USB_D-_30") (pintype "bidirectional"))
      (node (ref "R9") (pin "2") (pinfunction "2_2") (pintype "passive"))
    )
    (net (code "137") (name "/VIN") (class "Default")
      (node (ref "C15") (pin "1") (pinfunction "1_1") (pintype "passive"))
      (node (ref "D2") (pin "A") (pinfunction "A_A") (pintype "passive"))
      (node (ref "D2") (pin "C") (pinfunction "C_C") (pintype "passive"))
      (node (ref "IC2") (pin "3") (pinfunction "IN_3") (pintype "input"))
      (node (ref "PC1") (pin "+") (pinfunction "+_+") (pintype "passive"))
      (node (ref "POWER") (pin "8") (pinfunction "8_8") (pintype "passive"))
    )
    (net (code "138") (name "/X-DIR") (class "Default")
      (node (ref "IC1") (pin "80") (pinfunction "P0[5]/I2SRX_WS/TD2/CAP2[1]_80") (pintype "bidirectional"))
    )
    (net (code "139") (name "/X-EN") (class "Default")
      (node (ref "IC1") (pin "81") (pinfunction "P0[4]/I2SRX_CLK/RD2/CAP2[0]_81") (pintype "bidirectional"))
      (node (ref "XIO") (pin "20") (pinfunction "20_20") (pintype "passive"))
    )
    (net (code "140") (name "/X-MAX") (class "Default")
      (node (ref "IC1") (pin "39") (pinfunction "P1[25]/MC1A/MAT1[1]_39") (pintype "bidirectional"))
      (node (ref "PWML") (pin "3") (pinfunction "3_3") (pintype "passive"))
    )
    (net (code "141") (name "/X-MIN") (class "Default")
      (node (ref "IC1") (pin "38") (pinfunction "P1[24]/MCFB2/PWM1[5]/MOSI0_38") (pintype "bidirectional"))
      (node (ref "PWML") (pin "4") (pinfunction "4_4") (pintype "passive"))
    )
    (net (code "142") (name "/X-STEP") (class "Default")
      (node (ref "IC1") (pin "75") (pinfunction "P2[0]/PWM1[1]/TXD1_75") (pintype "bidirectional"))
    )
    (net (code "143") (name "/Y-DIR") (class "Default")
      (node (ref "IC1") (pin "49") (pinfunction "P0[11]/RXD2/SCL2/MAT3[1]_49") (pintype "bidirectional"))
    )
    (net (code "144") (name "/Y-EN") (class "Default")
      (node (ref "IC1") (pin "48") (pinfunction "P0[10]/TXD2/SDA2/MAT3[0]_48") (pintype "bidirectional"))
    )
    (net (code "145") (name "/Y-MAX") (class "Default")
      (node (ref "COMMUNICATION") (pin "7") (pinfunction "7_7") (pintype "passive"))
      (node (ref "IC1") (pin "43") (pinfunction "P1[27]/CLKOUT/USB_OVRCR/CAP0[1]_43") (pintype "bidirectional"))
    )
    (net (code "146") (name "/Y-MIN") (class "Default")
      (node (ref "COMMUNICATION") (pin "8") (pinfunction "8_8") (pintype "passive"))
      (node (ref "IC1") (pin "40") (pinfunction "P1[26]/MC1B/PWM1[6]/CAP0[0]_40") (pintype "bidirectional"))
    )
    (net (code "147") (name "/Y-STEP") (class "Default")
      (node (ref "IC1") (pin "74") (pinfunction "P2[1]/PWM1[2]/RXD1_74") (pintype "bidirectional"))
    )
    (net (code "148") (name "/Z-DIR") (class "Default")
      (node (ref "IC1") (pin "58") (pinfunction "P0[20]/DTR1/SCL1_58") (pintype "bidirectional"))
      (node (ref "XIO") (pin "29") (pinfunction "29_29") (pintype "passive"))
    )
    (net (code "149") (name "/Z-EN") (class "Default")
      (node (ref "IC1") (pin "59") (pinfunction "P0[19]/DSR1/SDA1_59") (pintype "bidirectional"))
    )
    (net (code "150") (name "/Z-MAX") (class "Default")
      (node (ref "COMMUNICATION") (pin "3") (pinfunction "3_3") (pintype "passive"))
      (node (ref "IC1") (pin "45") (pinfunction "P1[29]/MC2B/PCAP1[1]/MAT0[1]_45") (pintype "bidirectional"))
    )
    (net (code "151") (name "/Z-MIN") (class "Default")
      (node (ref "COMMUNICATION") (pin "4") (pinfunction "4_4") (pintype "passive"))
      (node (ref "IC1") (pin "44") (pinfunction "P1[28]/MC2A/PCAP1[0]/MAT0[0]_44") (pintype "bidirectional"))
    )
    (net (code "152") (name "/Z-STEP") (class "Default")
      (node (ref "IC1") (pin "73") (pinfunction "P2[2]/PWM1[3]/CTS1/TRACEDATA[3]_73") (pintype "bidirectional"))
      (node (ref "XIO") (pin "27") (pinfunction "27_27") (pintype "passive"))
    )
    (net (code "153") (name "3.3V") (class "Default")
      (node (ref "C1") (pin "2") (pinfunction "2_2") (pintype "passive"))
      (node (ref "C10") (pin "2") (pinfunction "2_2") (pintype "passive"))
      (node (ref "C11") (pin "2") (pinfunction "2_2") (pintype "passive"))
      (node (ref "C12") (pin "2") (pinfunction "2_2") (pintype "passive"))
      (node (ref "C13") (pin "2") (pinfunction "2_2") (pintype "passive"))
      (node (ref "C14") (pin "2") (pinfunction "2_2") (pintype "passive"))
      (node (ref "C65") (pin "1") (pinfunction "1_1") (pintype "passive"))
      (node (ref "C67") (pin "2") (pinfunction "2_2") (pintype "passive"))
      (node (ref "C7") (pin "A") (pinfunction "+_A") (pintype "passive"))
      (node (ref "C8") (pin "2") (pinfunction "2_2") (pintype "passive"))
      (node (ref "C9") (pin "2") (pinfunction "2_2") (pintype "passive"))
      (node (ref "IC1") (pin "19") (pinfunction "VBAT_19") (pintype "bidirectional"))
      (node (ref "IC1") (pin "28") (pinfunction "VDD(3V3)1_28") (pintype "bidirectional"))
      (node (ref "IC1") (pin "42") (pinfunction "VDD(REG)(3V3)1_42") (pintype "bidirectional"))
      (node (ref "IC1") (pin "54") (pinfunction "VDD(3V3)2_54") (pintype "bidirectional"))
      (node (ref "IC1") (pin "71") (pinfunction "VDD(3V3)3_71") (pintype "bidirectional"))
      (node (ref "IC1") (pin "84") (pinfunction "VDD(REG)(3V3)2_84") (pintype "bidirectional"))
      (node (ref "IC1") (pin "96") (pinfunction "VDD(3V3)4_96") (pintype "bidirectional"))
      (node (ref "IC10") (pin "2") (pinfunction "OUT_2") (pintype "output"))
      (node (ref "IC10") (pin "4") (pinfunction "OUT_4") (pintype "output"))
      (node (ref "L1") (pin "2") (pinfunction "2_2") (pintype "passive"))
      (node (ref "POWER") (pin "4") (pinfunction "4_4") (pintype "passive"))
      (node (ref "Q1") (pin "2") (pinfunction "S_2") (pintype "passive"))
      (node (ref "R1") (pin "2") (pinfunction "2_2") (pintype "passive"))
      (node (ref "R14") (pin "2") (pinfunction "2_2") (pintype "passive"))
      (node (ref "R15") (pin "2") (pinfunction "2_2") (pintype "passive"))
      (node (ref "R2") (pin "2") (pinfunction "2_2") (pintype "passive"))
      (node (ref "R3") (pin "2") (pinfunction "2_2") (pintype "passive"))
      (node (ref "R77") (pin "2") (pinfunction "2_2") (pintype "passive"))
      (node (ref "SJ1") (pin "1") (pinfunction "1_1") (pintype "passive"))
      (node (ref "SJ3") (pin "1") (pinfunction "1_1") (pintype "passive"))
      (node (ref "U1") (pin "4") (pinfunction "VCC_4") (pintype "bidirectional"))
    )
    (net (code "154") (name "5V") (class "Default")
      (node (ref "C16") (pin "2") (pinfunction "2_2") (pintype "passive"))
      (node (ref "C17") (pin "2") (pinfunction "2_2") (pintype "passive"))
      (node (ref "C64") (pin "A") (pinfunction "+_A") (pintype "passive"))
      (node (ref "D1") (pin "C") (pinfunction "C_C") (pintype "passive"))
      (node (ref "IC10") (pin "3") (pinfunction "IN_3") (pintype "input"))
      (node (ref "IC14") (pin "6") (pinfunction "P$1_6") (pintype "bidirectional"))
      (node (ref "IC15") (pin "6") (pinfunction "P$1_6") (pintype "bidirectional"))
      (node (ref "POWER") (pin "2") (pinfunction "2_2") (pintype "passive"))
      (node (ref "POWER") (pin "5") (pinfunction "5_5") (pintype "passive"))
      (node (ref "SJ1") (pin "3") (pinfunction "3_3") (pintype "passive"))
      (node (ref "SJ3") (pin "3") (pinfunction "3_3") (pintype "passive"))
      (node (ref "XIO") (pin "1") (pinfunction "1_1") (pintype "passive"))
      (node (ref "XIO") (pin "2") (pinfunction "2_2") (pintype "passive"))
    )
    (net (code "155") (name "AGND") (class "Default")
      (node (ref "IC1") (pin "11") (pinfunction "VSSA_11") (pintype "bidirectional"))
      (node (ref "IC1") (pin "15") (pinfunction "VREFN_15") (pintype "bidirectional"))
    )
    (net (code "156") (name "GND") (class "Default")
      (node (ref "C1") (pin "1") (pinfunction "1_1") (pintype "passive"))
      (node (ref "C10") (pin "1") (pinfunction "1_1") (pintype "passive"))
      (node (ref "C11") (pin "1") (pinfunction "1_1") (pintype "passive"))
      (node (ref "C12") (pin "1") (pinfunction "1_1") (pintype "passive"))
      (node (ref "C13") (pin "1") (pinfunction "1_1") (pintype "passive"))
      (node (ref "C14") (pin "1") (pinfunction "1_1") (pintype "passive"))
      (node (ref "C15") (pin "2") (pinfunction "2_2") (pintype "passive"))
      (node (ref "C16") (pin "1") (pinfunction "1_1") (pintype "passive"))
      (node (ref "C17") (pin "1") (pinfunction "1_1") (pintype "passive"))
      (node (ref "C2") (pin "2") (pinfunction "2_2") (pintype "passive"))
      (node (ref "C3") (pin "2") (pinfunction "2_2") (pintype "passive"))
      (node (ref "C4") (pin "1") (pinfunction "1_1") (pintype "passive"))
      (node (ref "C5") (pin "1") (pinfunction "1_1") (pintype "passive"))
      (node (ref "C6") (pin "2") (pinfunction "2_2") (pintype "passive"))
      (node (ref "C64") (pin "C") (pinfunction "-_C") (pintype "passive"))
      (node (ref "C65") (pin "2") (pinfunction "2_2") (pintype "passive"))
      (node (ref "C67") (pin "1") (pinfunction "1_1") (pintype "passive"))
      (node (ref "C7") (pin "C") (pinfunction "-_C") (pintype "passive"))
      (node (ref "C8") (pin "1") (pinfunction "1_1") (pintype "passive"))
      (node (ref "C9") (pin "1") (pinfunction "1_1") (pintype "passive"))
      (node (ref "IC1") (pin "31") (pinfunction "VSS1_31") (pintype "bidirectional"))
      (node (ref "IC1") (pin "41") (pinfunction "VSS2_41") (pintype "bidirectional"))
      (node (ref "IC1") (pin "55") (pinfunction "VSS3_55") (pintype "bidirectional"))
      (node (ref "IC1") (pin "72") (pinfunction "VSS4_72") (pintype "bidirectional"))
      (node (ref "IC1") (pin "83") (pinfunction "VSS6_83") (pintype "bidirectional"))
      (node (ref "IC1") (pin "97") (pinfunction "VSS5_97") (pintype "bidirectional"))
      (node (ref "IC10") (pin "1") (pinfunction "ADJ_1") (pintype "input"))
      (node (ref "IC14") (pin "3") (pinfunction "P$2_3") (pintype "bidirectional"))
      (node (ref "IC15") (pin "3") (pinfunction "P$2_3") (pintype "bidirectional"))
      (node (ref "IC2") (pin "1") (pinfunction "GND/ADJ_1") (pintype "input"))
      (node (ref "JP25") (pin "2") (pinfunction "2_2") (pintype "passive"))
      (node (ref "JP5") (pin "1") (pinfunction "1_1") (pintype "passive"))
      (node (ref "JP6") (pin "4") (pinfunction "4_4") (pintype "passive"))
      (node (ref "LED1") (pin "C") (pinfunction "C_C") (pintype "passive"))
      (node (ref "LED2") (pin "C") (pinfunction "C_C") (pintype "passive"))
      (node (ref "LED3") (pin "C") (pinfunction "C_C") (pintype "passive"))
      (node (ref "LED4") (pin "C") (pinfunction "C_C") (pintype "passive"))
      (node (ref "LED9") (pin "C") (pinfunction "C_C") (pintype "passive"))
      (node (ref "PC1") (pin "-") (pinfunction "-_-") (pintype "passive"))
      (node (ref "PC2") (pin "-") (pinfunction "-_-") (pintype "passive"))
      (node (ref "POWER") (pin "6") (pinfunction "6_6") (pintype "passive"))
      (node (ref "POWER") (pin "7") (pinfunction "7_7") (pintype "passive"))
      (node (ref "R71") (pin "1") (pinfunction "1_1") (pintype "passive"))
      (node (ref "R72") (pin "1") (pinfunction "1_1") (pintype "passive"))
      (node (ref "R87") (pin "1") (pinfunction "1_1") (pintype "passive"))
      (node (ref "S1") (pin "3") (pinfunction "3_3") (pintype "passive"))
      (node (ref "S1") (pin "4") (pinfunction "4_4") (pintype "passive"))
      (node (ref "S2") (pin "3") (pinfunction "3_3") (pintype "passive"))
      (node (ref "S2") (pin "4") (pinfunction "4_4") (pintype "passive"))
      (node (ref "U1") (pin "6") (pinfunction "GND_6") (pintype "bidirectional"))
      (node (ref "U1") (pin "CD2") (pinfunction "SHIELD_CD2") (pintype "bidirectional"))
      (node (ref "U1") (pin "GND1") (pinfunction "SHIELD_GND1") (pintype "bidirectional"))
      (node (ref "X2") (pin "4") (pinfunction "4_4") (pintype "bidirectional"))
      (node (ref "XIO") (pin "35") (pinfunction "35_35") (pintype "passive"))
      (node (ref "XIO") (pin "36") (pinfunction "36_36") (pintype "passive"))
    )
    (net (code "157") (name "Net-(IC1-XTAL1)") (class "Default")
      (node (ref "C2") (pin "1") (pinfunction "1_1") (pintype "passive"))
      (node (ref "IC1") (pin "22") (pinfunction "XTAL1_22") (pintype "bidirectional"))
      (node (ref "Q2") (pin "2") (pinfunction "2_2") (pintype "passive"))
    )
    (net (code "158") (name "Net-(IC1-XTAL2)") (class "Default")
      (node (ref "C3") (pin "1") (pinfunction "1_1") (pintype "passive"))
      (node (ref "IC1") (pin "23") (pinfunction "XTAL2_23") (pintype "bidirectional"))
      (node (ref "Q2") (pin "1") (pinfunction "1_1") (pintype "passive"))
    )
    (net (code "159") (name "Net-(IC14A-P$2)") (class "Default")
      (node (ref "IC14") (pin "7") (pinfunction "P$2_7") (pintype "bidirectional"))
      (node (ref "R69") (pin "1") (pinfunction "1_1") (pintype "passive"))
    )
    (net (code "160") (name "Net-(IC14B-P$2)") (class "Default")
      (node (ref "IC14") (pin "5") (pinfunction "P$2_5") (pintype "bidirectional"))
      (node (ref "R70") (pin "1") (pinfunction "1_1") (pintype "passive"))
    )
    (net (code "161") (name "Net-(IC15A-P$2)") (class "Default")
      (node (ref "IC15") (pin "7") (pinfunction "P$2_7") (pintype "bidirectional"))
      (node (ref "R4") (pin "1") (pinfunction "1_1") (pintype "passive"))
    )
    (net (code "162") (name "Net-(JP5-Pad3)") (class "Default")
      (node (ref "JP5") (pin "3") (pinfunction "3_3") (pintype "passive"))
      (node (ref "SJ1") (pin "2") (pinfunction "2_2") (pintype "passive"))
    )
    (net (code "163") (name "Net-(LED1-PadA)") (class "Default")
      (node (ref "LED1") (pin "A") (pinfunction "A_A") (pintype "passive"))
      (node (ref "R10") (pin "1") (pinfunction "1_1") (pintype "passive"))
    )
    (net (code "164") (name "Net-(LED2-PadA)") (class "Default")
      (node (ref "LED2") (pin "A") (pinfunction "A_A") (pintype "passive"))
      (node (ref "R11") (pin "1") (pinfunction "1_1") (pintype "passive"))
    )
    (net (code "165") (name "Net-(LED3-PadA)") (class "Default")
      (node (ref "LED3") (pin "A") (pinfunction "A_A") (pintype "passive"))
      (node (ref "R12") (pin "1") (pinfunction "1_1") (pintype "passive"))
    )
    (net (code "166") (name "Net-(LED4-PadA)") (class "Default")
      (node (ref "LED4") (pin "A") (pinfunction "A_A") (pintype "passive"))
      (node (ref "R13") (pin "1") (pinfunction "1_1") (pintype "passive"))
    )
    (net (code "167") (name "Net-(LED9-PadA)") (class "Default")
      (node (ref "LED9") (pin "A") (pinfunction "A_A") (pintype "passive"))
      (node (ref "R77") (pin "1") (pinfunction "1_1") (pintype "passive"))
    )
    (net (code "168") (name "Net-(Q1-D)") (class "Default")
      (node (ref "Q1") (pin "3") (pinfunction "D_3") (pintype "passive"))
      (node (ref "R7") (pin "2") (pinfunction "2_2") (pintype "passive"))
    )
    (net (code "169") (name "Net-(R5-Pad2)") (class "Default")
      (node (ref "R5") (pin "2") (pinfunction "2_2") (pintype "passive"))
      (node (ref "R6") (pin "2") (pinfunction "2_2") (pintype "passive"))
      (node (ref "SJ3") (pin "2") (pinfunction "2_2") (pintype "passive"))
    )
    (net (code "170") (name "Net-(R8-Pad1)") (class "Default")
      (node (ref "R8") (pin "1") (pinfunction "1_1") (pintype "passive"))
      (node (ref "X2") (pin "1") (pinfunction "1_1") (pintype "bidirectional"))
    )
    (net (code "171") (name "Net-(R9-Pad1)") (class "Default")
      (node (ref "R9") (pin "1") (pinfunction "1_1") (pintype "passive"))
      (node (ref "X2") (pin "2") (pinfunction "2_2") (pintype "bidirectional"))
    )
    (net (code "172") (name "VUSB") (class "Default")
      (node (ref "D1") (pin "A") (pinfunction "A_A") (pintype "passive"))
      (node (ref "X2") (pin "3") (pinfunction "3_3") (pintype "bidirectional"))
    )
    (net (code "173") (name "unconnected-(IC1-N.C.-Pad13)") (class "Default")
      (node (ref "IC1") (pin "13") (pinfunction "N.C._13") (pintype "bidirectional"))
    )
    (net (code "174") (name "unconnected-(IC1-RTCX1-Pad16)") (class "Default")
      (node (ref "IC1") (pin "16") (pinfunction "RTCX1_16") (pintype "bidirectional"))
    )
    (net (code "175") (name "unconnected-(IC1-RTCX2-Pad18)") (class "Default")
      (node (ref "IC1") (pin "18") (pinfunction "RTCX2_18") (pintype "bidirectional"))
    )
    (net (code "176") (name "unconnected-(POWER-Pad1)") (class "Default")
      (node (ref "POWER") (pin "1") (pinfunction "1_1") (pintype "passive"))
    )
    (net (code "177") (name "unconnected-(U1-NC-Pad1)") (class "Default")
      (node (ref "U1") (pin "1") (pinfunction "NC_1") (pintype "bidirectional"))
    )
    (net (code "178") (name "unconnected-(U1-RSV-Pad8)") (class "Default")
      (node (ref "U1") (pin "8") (pinfunction "RSV_8") (pintype "bidirectional"))
    )
    (net (code "179") (name "unconnected-(U1-SHIELD-PadCD1)") (class "Default")
      (node (ref "U1") (pin "CD1") (pinfunction "SHIELD_CD1") (pintype "bidirectional"))
    )
    (net (code "180") (name "unconnected-(U1-SHIELD-PadGND3)") (class "Default")
      (node (ref "U1") (pin "GND3") (pinfunction "SHIELD_GND3") (pintype "bidirectional"))
    )
    (net (code "181") (name "unconnected-(X2-PadP$1)") (class "Default")
      (node (ref "X2") (pin "P$1") (pinfunction "P$1_P$1") (pintype "bidirectional"))
    )
    (net (code "182") (name "unconnected-(X2-PadP$2)") (class "Default")
      (node (ref "X2") (pin "P$2") (pinfunction "P$2_P$2") (pintype "bidirectional"))
    )
  )
)
